# EEPromCap.net
KiCad netlist of a schematic drawn in EAGLE
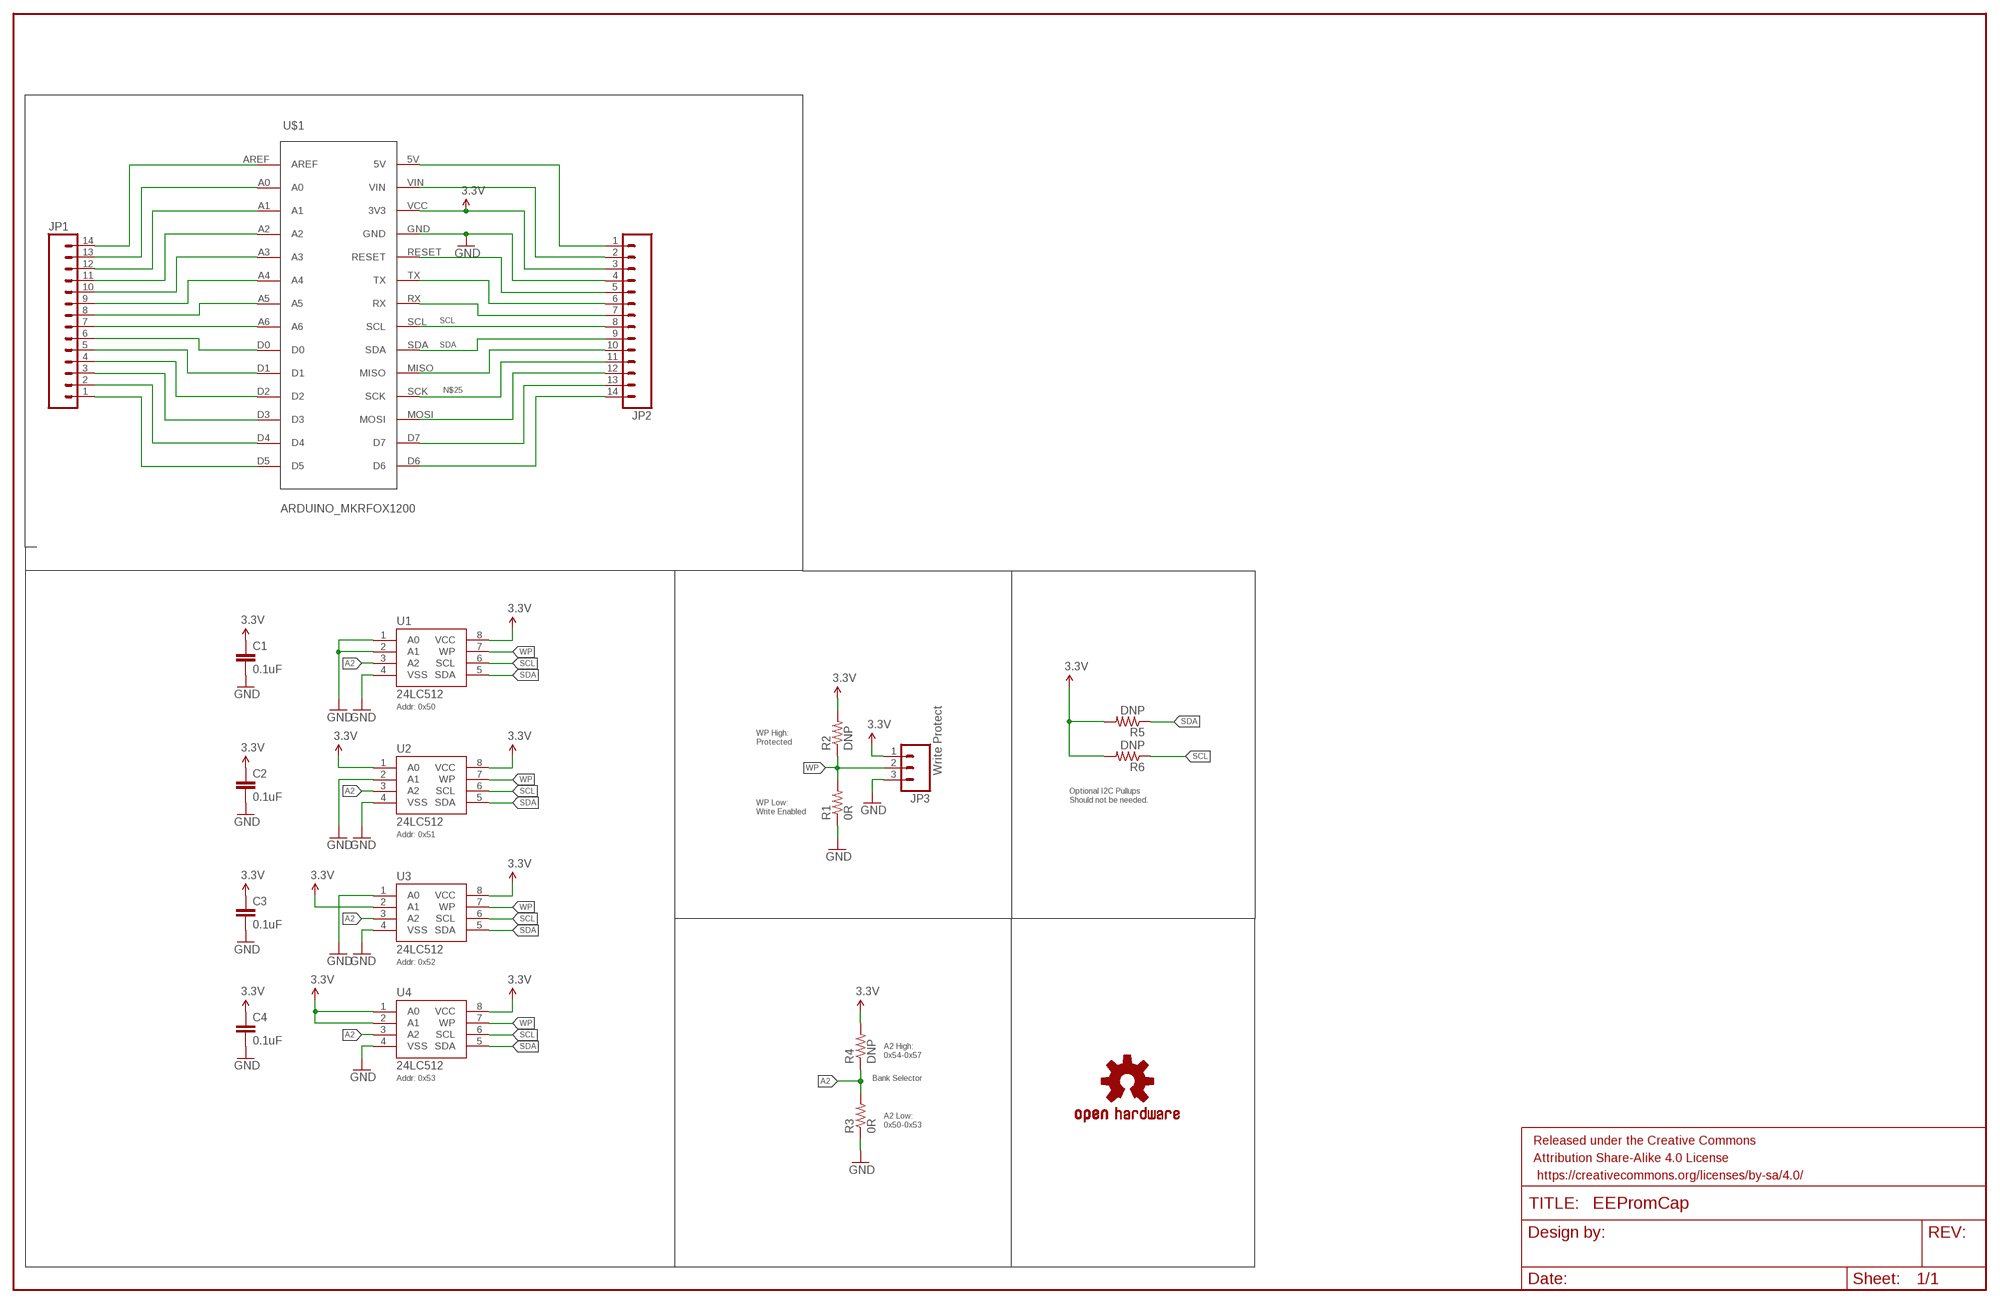
[diagram p0: schematic, sheet 1]

(export (version "E")
  (design (tool "Eeschema 10.0.6"))
  (components
    (comp (ref "C1")
      (value "0.1uF")
      (footprint "eagle-import:1206")
      (libsource (lib "eagle-import") (part "CAP1206"))
    )
    (comp (ref "C2")
      (value "0.1uF")
      (footprint "eagle-import:1206")
      (libsource (lib "eagle-import") (part "CAP1206"))
    )
    (comp (ref "C3")
      (value "0.1uF")
      (footprint "eagle-import:1206")
      (libsource (lib "eagle-import") (part "CAP1206"))
    )
    (comp (ref "C4")
      (value "0.1uF")
      (footprint "eagle-import:1206")
      (libsource (lib "eagle-import") (part "CAP1206"))
    )
    (comp (ref "FRAME1")
      (value "FRAME-LEDGER")
      (footprint "eagle-import:CREATIVE_COMMONS")
      (libsource (lib "eagle-import") (part "FRAME-LEDGER"))
    )
    (comp (ref "JP1")
      (value "M14")
      (footprint "eagle-import:1X14")
      (libsource (lib "eagle-import") (part "M14"))
    )
    (comp (ref "JP2")
      (value "M14")
      (footprint "eagle-import:1X14")
      (libsource (lib "eagle-import") (part "M14"))
    )
    (comp (ref "JP3")
      (value "Write Protect")
      (footprint "eagle-import:1X03")
      (libsource (lib "eagle-import") (part "M03PTH"))
    )
    (comp (ref "LOGO2")
      (value "OSHW-LOGOM")
      (footprint "eagle-import:OSHW-LOGO-M")
      (libsource (lib "eagle-import") (part "OSHW-LOGOM"))
    )
    (comp (ref "R1")
      (value "0R")
      (footprint "eagle-import:1206")
      (libsource (lib "eagle-import") (part "RESISTOR1206"))
    )
    (comp (ref "R2")
      (value "DNP")
      (footprint "eagle-import:1206")
      (libsource (lib "eagle-import") (part "RESISTOR1206"))
    )
    (comp (ref "R3")
      (value "0R")
      (footprint "eagle-import:1206")
      (libsource (lib "eagle-import") (part "RESISTOR1206"))
    )
    (comp (ref "R4")
      (value "DNP")
      (footprint "eagle-import:1206")
      (libsource (lib "eagle-import") (part "RESISTOR1206"))
    )
    (comp (ref "R5")
      (value "DNP")
      (footprint "eagle-import:0805")
      (libsource (lib "eagle-import") (part "RESISTOR0805-RES"))
    )
    (comp (ref "R6")
      (value "DNP")
      (footprint "eagle-import:0805")
      (libsource (lib "eagle-import") (part "RESISTOR0805-RES"))
    )
    (comp (ref "U$1")
      (value "ARDUINO_MKRFOX1200")
      (footprint "eagle-import:ARDUINO_MKRFOX1200")
      (libsource (lib "eagle-import") (part "ARDUINO_MKRFOX1200"))
    )
    (comp (ref "U1")
      (value "24LC512")
      (footprint "eagle-import:SO08")
      (libsource (lib "eagle-import") (part "EEPROM-I2CSMD"))
    )
    (comp (ref "U2")
      (value "24LC512")
      (footprint "eagle-import:SO08")
      (libsource (lib "eagle-import") (part "EEPROM-I2CSMD"))
    )
    (comp (ref "U3")
      (value "24LC512")
      (footprint "eagle-import:SO08")
      (libsource (lib "eagle-import") (part "EEPROM-I2CSMD"))
    )
    (comp (ref "U4")
      (value "24LC512")
      (footprint "eagle-import:SO08")
      (libsource (lib "eagle-import") (part "EEPROM-I2CSMD"))
    )
  )
  (nets
    (net (code "1") (name "/N$25") (class "Default")
      (node (ref "JP2") (pin "11") (pinfunction "11_11") (pintype "passive"))
      (node (ref "U$1") (pin "SCK") (pinfunction "SCK_SCK") (pintype "bidirectional"))
    )
    (net (code "2") (name "3.3V") (class "Default")
      (node (ref "C1") (pin "1") (pinfunction "1_1") (pintype "passive"))
      (node (ref "C2") (pin "1") (pinfunction "1_1") (pintype "passive"))
      (node (ref "C3") (pin "1") (pinfunction "1_1") (pintype "passive"))
      (node (ref "C4") (pin "1") (pinfunction "1_1") (pintype "passive"))
      (node (ref "JP2") (pin "3") (pinfunction "3_3") (pintype "passive"))
      (node (ref "JP3") (pin "1") (pinfunction "1_1") (pintype "passive"))
      (node (ref "R2") (pin "2") (pinfunction "2_2") (pintype "passive"))
      (node (ref "R4") (pin "2") (pinfunction "2_2") (pintype "passive"))
      (node (ref "R5") (pin "2") (pinfunction "2_2") (pintype "passive"))
      (node (ref "R6") (pin "2") (pinfunction "2_2") (pintype "passive"))
      (node (ref "U$1") (pin "VCC") (pinfunction "3V3_VCC") (pintype "output"))
      (node (ref "U1") (pin "8") (pinfunction "VCC_8") (pintype "power_in"))
      (node (ref "U2") (pin "1") (pinfunction "A0_1") (pintype "bidirectional"))
      (node (ref "U2") (pin "8") (pinfunction "VCC_8") (pintype "power_in"))
      (node (ref "U3") (pin "2") (pinfunction "A1_2") (pintype "bidirectional"))
      (node (ref "U3") (pin "8") (pinfunction "VCC_8") (pintype "power_in"))
      (node (ref "U4") (pin "1") (pinfunction "A0_1") (pintype "bidirectional"))
      (node (ref "U4") (pin "2") (pinfunction "A1_2") (pintype "bidirectional"))
      (node (ref "U4") (pin "8") (pinfunction "VCC_8") (pintype "power_in"))
    )
    (net (code "3") (name "A2") (class "Default")
      (node (ref "R3") (pin "2") (pinfunction "2_2") (pintype "passive"))
      (node (ref "R4") (pin "1") (pinfunction "1_1") (pintype "passive"))
      (node (ref "U1") (pin "3") (pinfunction "A2_3") (pintype "bidirectional"))
      (node (ref "U2") (pin "3") (pinfunction "A2_3") (pintype "bidirectional"))
      (node (ref "U3") (pin "3") (pinfunction "A2_3") (pintype "bidirectional"))
      (node (ref "U4") (pin "3") (pinfunction "A2_3") (pintype "bidirectional"))
    )
    (net (code "4") (name "GND") (class "Default")
      (node (ref "C1") (pin "2") (pinfunction "2_2") (pintype "passive"))
      (node (ref "C2") (pin "2") (pinfunction "2_2") (pintype "passive"))
      (node (ref "C3") (pin "2") (pinfunction "2_2") (pintype "passive"))
      (node (ref "C4") (pin "2") (pinfunction "2_2") (pintype "passive"))
      (node (ref "JP2") (pin "4") (pinfunction "4_4") (pintype "passive"))
      (node (ref "JP3") (pin "3") (pinfunction "3_3") (pintype "passive"))
      (node (ref "R1") (pin "1") (pinfunction "1_1") (pintype "passive"))
      (node (ref "R3") (pin "1") (pinfunction "1_1") (pintype "passive"))
      (node (ref "U$1") (pin "GND") (pinfunction "GND_GND") (pintype "power_in"))
      (node (ref "U1") (pin "1") (pinfunction "A0_1") (pintype "bidirectional"))
      (node (ref "U1") (pin "2") (pinfunction "A1_2") (pintype "bidirectional"))
      (node (ref "U1") (pin "4") (pinfunction "VSS_4") (pintype "power_in"))
      (node (ref "U2") (pin "2") (pinfunction "A1_2") (pintype "bidirectional"))
      (node (ref "U2") (pin "4") (pinfunction "VSS_4") (pintype "power_in"))
      (node (ref "U3") (pin "1") (pinfunction "A0_1") (pintype "bidirectional"))
      (node (ref "U3") (pin "4") (pinfunction "VSS_4") (pintype "power_in"))
      (node (ref "U4") (pin "4") (pinfunction "VSS_4") (pintype "power_in"))
    )
    (net (code "5") (name "Net-(JP1-Pad1)") (class "Default")
      (node (ref "JP1") (pin "1") (pinfunction "1_1") (pintype "passive"))
      (node (ref "U$1") (pin "D5") (pinfunction "D5_D5") (pintype "bidirectional"))
    )
    (net (code "6") (name "Net-(JP1-Pad2)") (class "Default")
      (node (ref "JP1") (pin "2") (pinfunction "2_2") (pintype "passive"))
      (node (ref "U$1") (pin "D4") (pinfunction "D4_D4") (pintype "bidirectional"))
    )
    (net (code "7") (name "Net-(JP1-Pad3)") (class "Default")
      (node (ref "JP1") (pin "3") (pinfunction "3_3") (pintype "passive"))
      (node (ref "U$1") (pin "D3") (pinfunction "D3_D3") (pintype "bidirectional"))
    )
    (net (code "8") (name "Net-(JP1-Pad4)") (class "Default")
      (node (ref "JP1") (pin "4") (pinfunction "4_4") (pintype "passive"))
      (node (ref "U$1") (pin "D2") (pinfunction "D2_D2") (pintype "bidirectional"))
    )
    (net (code "9") (name "Net-(JP1-Pad5)") (class "Default")
      (node (ref "JP1") (pin "5") (pinfunction "5_5") (pintype "passive"))
      (node (ref "U$1") (pin "D1") (pinfunction "D1_D1") (pintype "bidirectional"))
    )
    (net (code "10") (name "Net-(JP1-Pad6)") (class "Default")
      (node (ref "JP1") (pin "6") (pinfunction "6_6") (pintype "passive"))
      (node (ref "U$1") (pin "D0") (pinfunction "D0_D0") (pintype "bidirectional"))
    )
    (net (code "11") (name "Net-(JP1-Pad7)") (class "Default")
      (node (ref "JP1") (pin "7") (pinfunction "7_7") (pintype "passive"))
      (node (ref "U$1") (pin "A6") (pinfunction "A6_A6") (pintype "bidirectional"))
    )
    (net (code "12") (name "Net-(JP1-Pad8)") (class "Default")
      (node (ref "JP1") (pin "8") (pinfunction "8_8") (pintype "passive"))
      (node (ref "U$1") (pin "A5") (pinfunction "A5_A5") (pintype "bidirectional"))
    )
    (net (code "13") (name "Net-(JP1-Pad9)") (class "Default")
      (node (ref "JP1") (pin "9") (pinfunction "9_9") (pintype "passive"))
      (node (ref "U$1") (pin "A4") (pinfunction "A4_A4") (pintype "bidirectional"))
    )
    (net (code "14") (name "Net-(JP1-Pad10)") (class "Default")
      (node (ref "JP1") (pin "10") (pinfunction "10_10") (pintype "passive"))
      (node (ref "U$1") (pin "A3") (pinfunction "A3_A3") (pintype "bidirectional"))
    )
    (net (code "15") (name "Net-(JP1-Pad11)") (class "Default")
      (node (ref "JP1") (pin "11") (pinfunction "11_11") (pintype "passive"))
      (node (ref "U$1") (pin "A2") (pinfunction "A2_A2") (pintype "bidirectional"))
    )
    (net (code "16") (name "Net-(JP1-Pad12)") (class "Default")
      (node (ref "JP1") (pin "12") (pinfunction "12_12") (pintype "passive"))
      (node (ref "U$1") (pin "A1") (pinfunction "A1_A1") (pintype "bidirectional"))
    )
    (net (code "17") (name "Net-(JP1-Pad13)") (class "Default")
      (node (ref "JP1") (pin "13") (pinfunction "13_13") (pintype "passive"))
      (node (ref "U$1") (pin "A0") (pinfunction "A0_A0") (pintype "bidirectional"))
    )
    (net (code "18") (name "Net-(JP1-Pad14)") (class "Default")
      (node (ref "JP1") (pin "14") (pinfunction "14_14") (pintype "passive"))
      (node (ref "U$1") (pin "AREF") (pinfunction "AREF_AREF") (pintype "bidirectional"))
    )
    (net (code "19") (name "Net-(JP2-Pad1)") (class "Default")
      (node (ref "JP2") (pin "1") (pinfunction "1_1") (pintype "passive"))
      (node (ref "U$1") (pin "5V") (pinfunction "5V_5V") (pintype "output"))
    )
    (net (code "20") (name "Net-(JP2-Pad2)") (class "Default")
      (node (ref "JP2") (pin "2") (pinfunction "2_2") (pintype "passive"))
      (node (ref "U$1") (pin "VIN") (pinfunction "VIN_VIN") (pintype "input"))
    )
    (net (code "21") (name "Net-(JP2-Pad5)") (class "Default")
      (node (ref "JP2") (pin "5") (pinfunction "5_5") (pintype "passive"))
      (node (ref "U$1") (pin "RESET") (pinfunction "RESET_RESET") (pintype "bidirectional"))
    )
    (net (code "22") (name "Net-(JP2-Pad6)") (class "Default")
      (node (ref "JP2") (pin "6") (pinfunction "6_6") (pintype "passive"))
      (node (ref "U$1") (pin "TX") (pinfunction "TX_TX") (pintype "bidirectional"))
    )
    (net (code "23") (name "Net-(JP2-Pad7)") (class "Default")
      (node (ref "JP2") (pin "7") (pinfunction "7_7") (pintype "passive"))
      (node (ref "U$1") (pin "RX") (pinfunction "RX_RX") (pintype "bidirectional"))
    )
    (net (code "24") (name "Net-(JP2-Pad10)") (class "Default")
      (node (ref "JP2") (pin "10") (pinfunction "10_10") (pintype "passive"))
      (node (ref "U$1") (pin "MISO") (pinfunction "MISO_MISO") (pintype "bidirectional"))
    )
    (net (code "25") (name "Net-(JP2-Pad12)") (class "Default")
      (node (ref "JP2") (pin "12") (pinfunction "12_12") (pintype "passive"))
      (node (ref "U$1") (pin "MOSI") (pinfunction "MOSI_MOSI") (pintype "bidirectional"))
    )
    (net (code "26") (name "Net-(JP2-Pad13)") (class "Default")
      (node (ref "JP2") (pin "13") (pinfunction "13_13") (pintype "passive"))
      (node (ref "U$1") (pin "D7") (pinfunction "D7_D7") (pintype "bidirectional"))
    )
    (net (code "27") (name "Net-(JP2-Pad14)") (class "Default")
      (node (ref "JP2") (pin "14") (pinfunction "14_14") (pintype "passive"))
      (node (ref "U$1") (pin "D6") (pinfunction "D6_D6") (pintype "bidirectional"))
    )
    (net (code "28") (name "SCL") (class "Default")
      (node (ref "JP2") (pin "8") (pinfunction "8_8") (pintype "passive"))
      (node (ref "R6") (pin "1") (pinfunction "1_1") (pintype "passive"))
      (node (ref "U$1") (pin "SCL") (pinfunction "SCL_SCL") (pintype "bidirectional"))
      (node (ref "U1") (pin "6") (pinfunction "SCL_6") (pintype "bidirectional"))
      (node (ref "U2") (pin "6") (pinfunction "SCL_6") (pintype "bidirectional"))
      (node (ref "U3") (pin "6") (pinfunction "SCL_6") (pintype "bidirectional"))
      (node (ref "U4") (pin "6") (pinfunction "SCL_6") (pintype "bidirectional"))
    )
    (net (code "29") (name "SDA") (class "Default")
      (node (ref "JP2") (pin "9") (pinfunction "9_9") (pintype "passive"))
      (node (ref "R5") (pin "1") (pinfunction "1_1") (pintype "passive"))
      (node (ref "U$1") (pin "SDA") (pinfunction "SDA_SDA") (pintype "bidirectional"))
      (node (ref "U1") (pin "5") (pinfunction "SDA_5") (pintype "bidirectional"))
      (node (ref "U2") (pin "5") (pinfunction "SDA_5") (pintype "bidirectional"))
      (node (ref "U3") (pin "5") (pinfunction "SDA_5") (pintype "bidirectional"))
      (node (ref "U4") (pin "5") (pinfunction "SDA_5") (pintype "bidirectional"))
    )
    (net (code "30") (name "WP") (class "Default")
      (node (ref "JP3") (pin "2") (pinfunction "2_2") (pintype "passive"))
      (node (ref "R1") (pin "2") (pinfunction "2_2") (pintype "passive"))
      (node (ref "R2") (pin "1") (pinfunction "1_1") (pintype "passive"))
      (node (ref "U1") (pin "7") (pinfunction "WP_7") (pintype "bidirectional"))
      (node (ref "U2") (pin "7") (pinfunction "WP_7") (pintype "bidirectional"))
      (node (ref "U3") (pin "7") (pinfunction "WP_7") (pintype "bidirectional"))
      (node (ref "U4") (pin "7") (pinfunction "WP_7") (pintype "bidirectional"))
    )
  )
)
